# Flash.net
KiCad netlist of a schematic drawn in Altium Designer
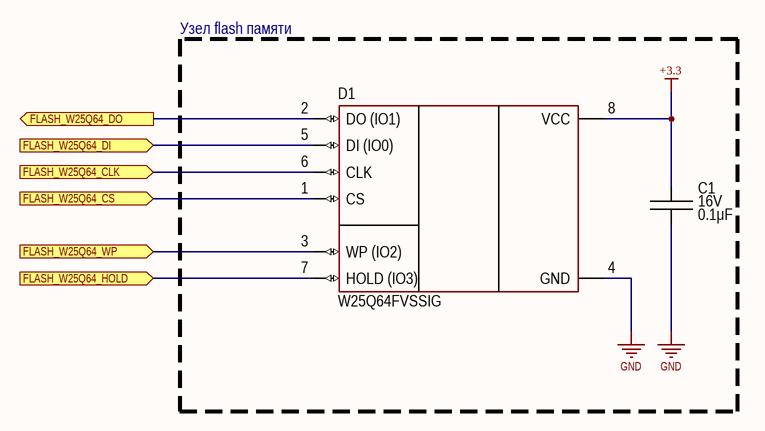
[diagram p0: Flash.SchDoc]

(export (version "E")
  (design (tool "Eeschema 10.0.6"))
  (components
    (comp (ref "C1")
      (value "0.1μF")
      (footprint "CAP: 0603")
      (fields
        (field (name "MANUFACTURER") "Yageo")
        (field (name "PARTNUMBER") "CC0603KRX7R7BB104")
        (field (name "VALUEMANUFACTURERPARTNUMBER") "Ceramic capacitor, 0.1μF, X7R, ±10%, 16V, 0603, -55...+125°C")
        (field (name "VOLTAGE") "16V")
      )
      (libsource (lib "capacitor") (part "Ceramic_0603"))
    )
    (comp (ref "D1")
      (value "~")
      (footprint "8-SOIC")
      (description "FLASH")
      (fields
        (field (name "MANUFACTURER") "Winbond Electronics")
        (field (name "VALUEMANUFACTURERPARTNUMBER") "IC memory, FLASH, 64Mb (8M x 8), 104 MHz, SPI/QuadSPI, 2.7...3.6V, -40...+85°C, 8-SOIC")
        (field (name "PARTNUMBER") "W25Q64FVSSIG")
      )
      (libsource (lib "ic-memory") (part "W25Q64FVSSIG"))
    )
  )
  (nets
    (net (code "1") (name "+3.3") (class "Default")
      (node (ref "C1") (pin "1") (pinfunction "1_1") (pintype "passive"))
      (node (ref "D1") (pin "8") (pinfunction "VCC_8") (pintype "power_in"))
    )
    (net (code "2") (name "/FLASH_W25Q64_CLK") (class "Default")
      (node (ref "D1") (pin "6") (pinfunction "CLK_6") (pintype "bidirectional"))
    )
    (net (code "3") (name "/FLASH_W25Q64_CS") (class "Default")
      (node (ref "D1") (pin "1") (pinfunction "CS_1") (pintype "bidirectional"))
    )
    (net (code "4") (name "/FLASH_W25Q64_DI") (class "Default")
      (node (ref "D1") (pin "5") (pinfunction "DI_(IO0)_5") (pintype "bidirectional"))
    )
    (net (code "5") (name "/FLASH_W25Q64_DO") (class "Default")
      (node (ref "D1") (pin "2") (pinfunction "DO_(IO1)_2") (pintype "bidirectional"))
    )
    (net (code "6") (name "/FLASH_W25Q64_HOLD") (class "Default")
      (node (ref "D1") (pin "7") (pinfunction "HOLD_(IO3)_7") (pintype "bidirectional"))
    )
    (net (code "7") (name "/FLASH_W25Q64_WP") (class "Default")
      (node (ref "D1") (pin "3") (pinfunction "WP_(IO2)_3") (pintype "bidirectional"))
    )
    (net (code "8") (name "GND") (class "Default")
      (node (ref "C1") (pin "2") (pinfunction "2_2") (pintype "passive"))
      (node (ref "D1") (pin "4") (pinfunction "GND_4") (pintype "power_in"))
    )
  )
)
